# TopLevel.net
KiCad netlist of a schematic drawn in Altium Designer
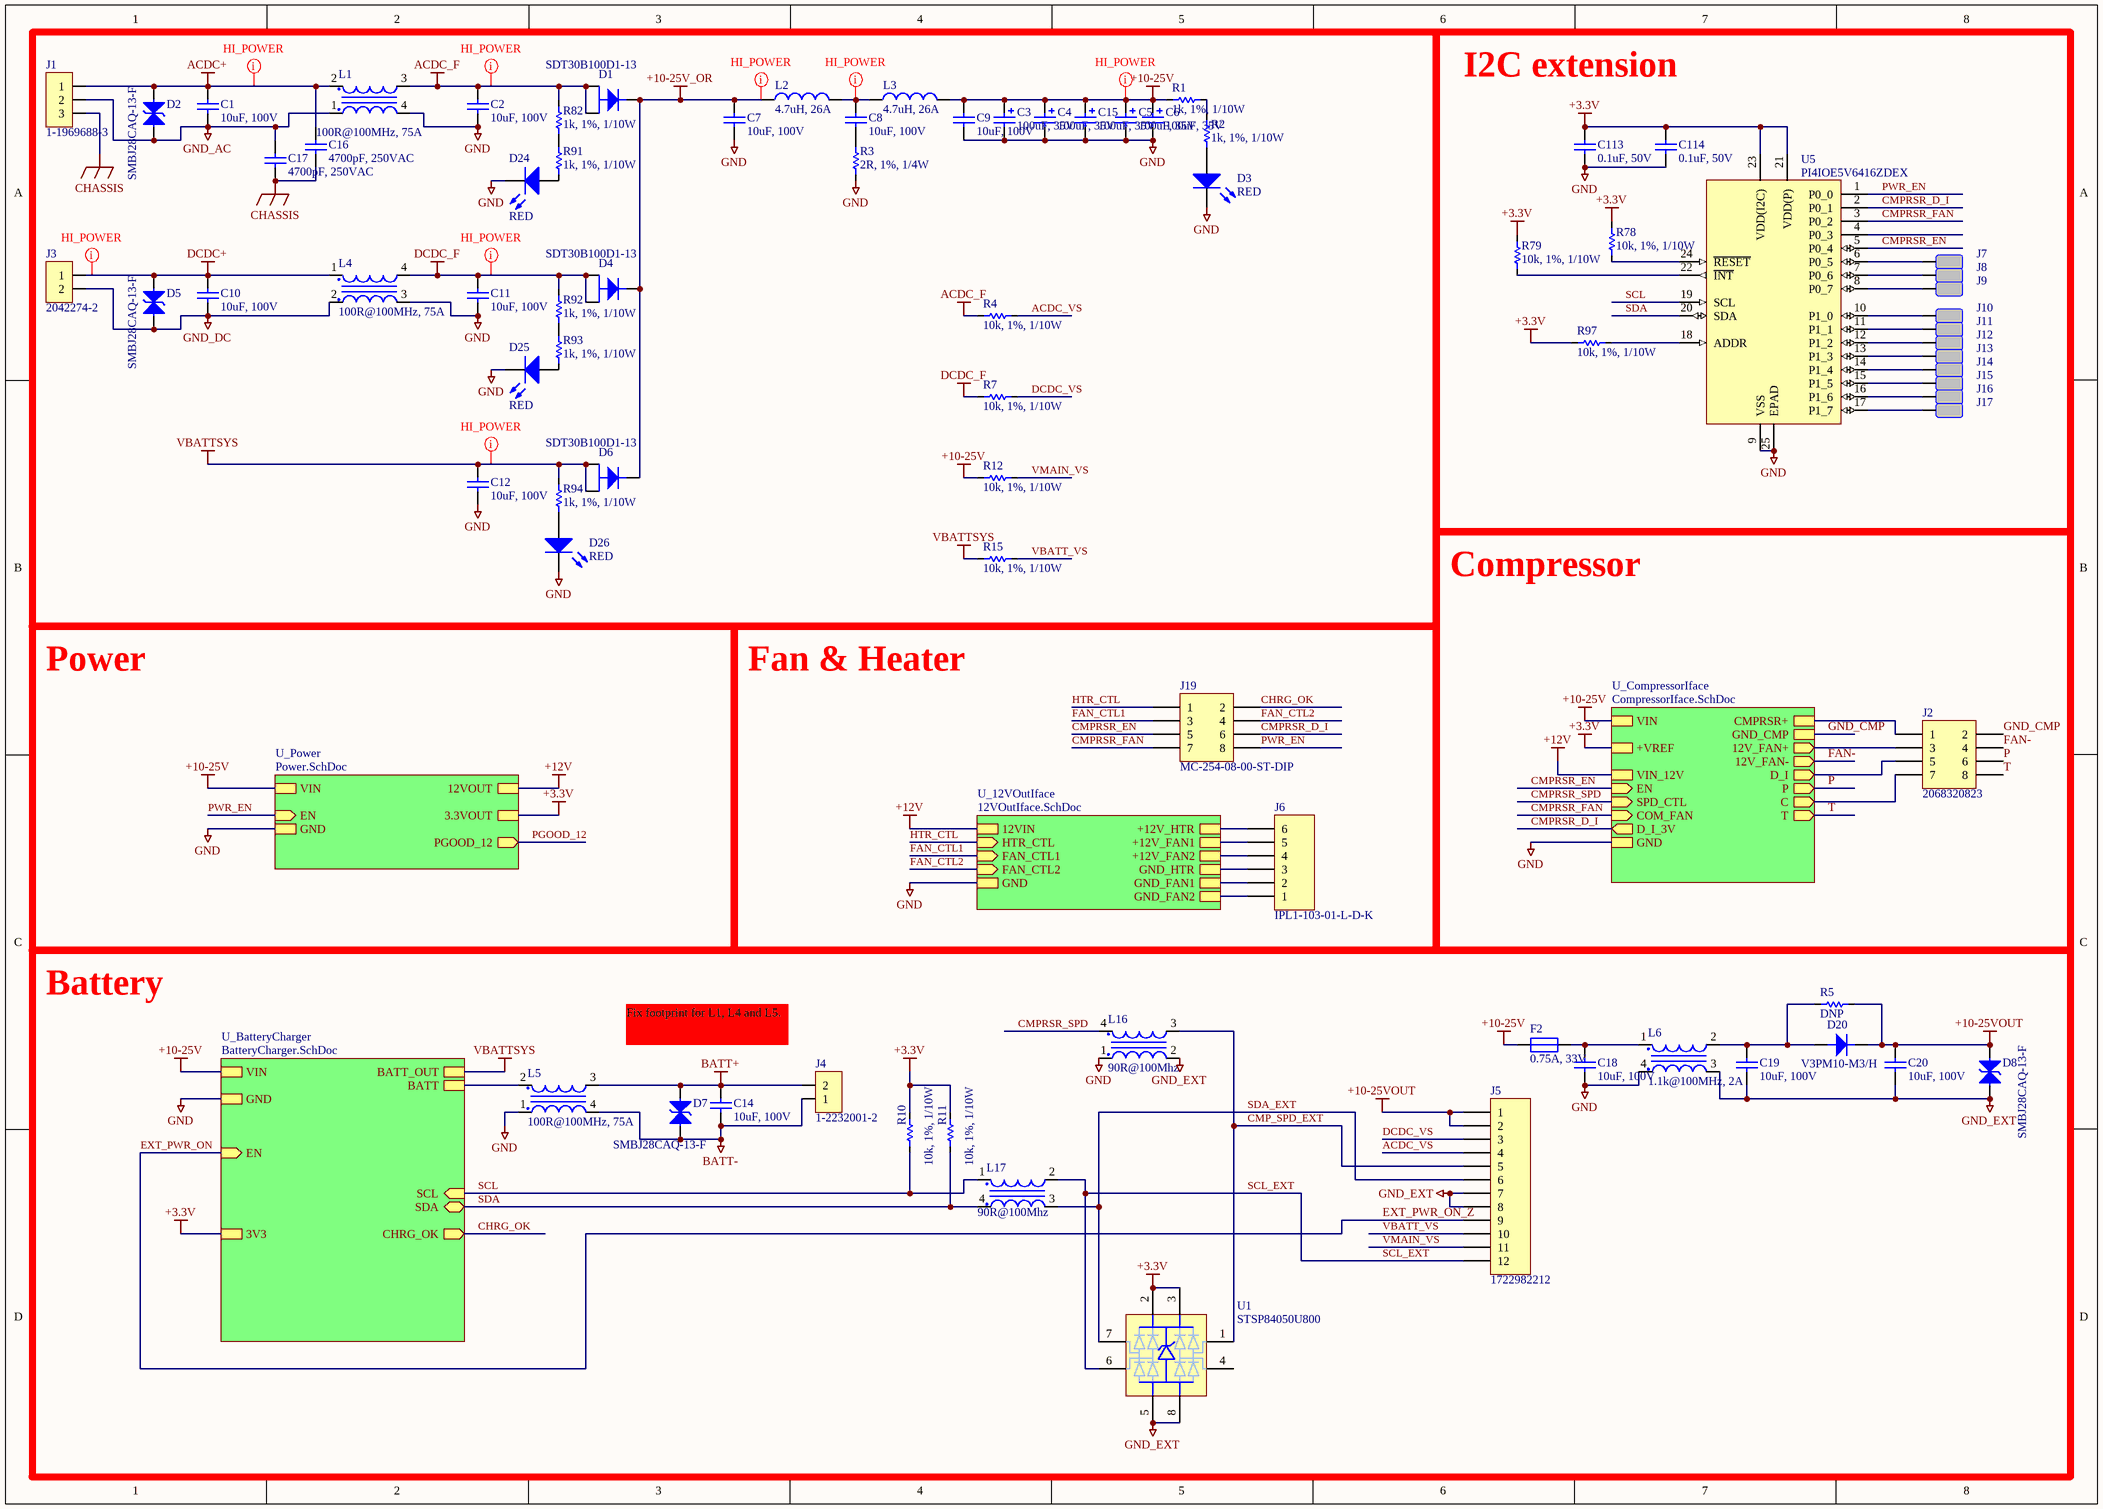
[diagram p0: TopLevel.SchDoc]

(export (version "E")
  (design (tool "Eeschema 10.0.6"))
  (components
    (comp (ref "C1")
      (value "10uF, 100V")
      (footprint "1210")
      (description "MLCC 10UF 100V X7S 1210")
      (fields (field (name "PART NUMBER") "NS00779"))
      (libsource (lib "FullPartsDB") (part "Cap"))
    )
    (comp (ref "C2")
      (value "10uF, 100V")
      (footprint "1210")
      (description "MLCC 10UF 100V X7S 1210")
      (fields (field (name "PART NUMBER") "NS00779"))
      (libsource (lib "FullPartsDB") (part "Cap"))
    )
    (comp (ref "C3")
      (value "100uF, 35V")
      (footprint "CAPAE7866X80L")
      (description "CAP ALUM 100UF 20% 35V SMD")
      (fields (field (name "PART NUMBER") "NS00911"))
      (libsource (lib "FullPartsDB") (part "CAP_POL"))
    )
    (comp (ref "C4")
      (value "100uF, 35V")
      (footprint "CAPAE7866X80L")
      (description "CAP ALUM 100UF 20% 35V SMD")
      (fields (field (name "PART NUMBER") "NS00911"))
      (libsource (lib "FullPartsDB") (part "CAP_POL"))
    )
    (comp (ref "C5")
      (value "100uF, 35V")
      (footprint "CAPAE7866X80L")
      (description "CAP ALUM 100UF 20% 35V SMD")
      (fields (field (name "PART NUMBER") "NS00911"))
      (libsource (lib "FullPartsDB") (part "CAP_POL"))
    )
    (comp (ref "C6")
      (value "100uF, 35V")
      (footprint "CAPAE7866X80L")
      (description "CAP ALUM 100UF 20% 35V SMD")
      (fields (field (name "PART NUMBER") "NS00911"))
      (libsource (lib "FullPartsDB") (part "CAP_POL"))
    )
    (comp (ref "C7")
      (value "10uF, 100V")
      (footprint "1210")
      (description "MLCC 10UF 100V X7S 1210")
      (fields (field (name "PART NUMBER") "NS00779"))
      (libsource (lib "FullPartsDB") (part "Cap"))
    )
    (comp (ref "C8")
      (value "10uF, 100V")
      (footprint "1210")
      (description "MLCC 10UF 100V X7S 1210")
      (fields (field (name "PART NUMBER") "NS00779"))
      (libsource (lib "FullPartsDB") (part "Cap"))
    )
    (comp (ref "C9")
      (value "10uF, 100V")
      (footprint "1210")
      (description "MLCC 10UF 100V X7S 1210")
      (fields (field (name "PART NUMBER") "NS00779"))
      (libsource (lib "FullPartsDB") (part "Cap"))
    )
    (comp (ref "C10")
      (value "10uF, 100V")
      (footprint "1210")
      (description "MLCC 10UF 100V X7S 1210")
      (fields (field (name "PART NUMBER") "NS00779"))
      (libsource (lib "FullPartsDB") (part "Cap"))
    )
    (comp (ref "C11")
      (value "10uF, 100V")
      (footprint "1210")
      (description "MLCC 10UF 100V X7S 1210")
      (fields (field (name "PART NUMBER") "NS00779"))
      (libsource (lib "FullPartsDB") (part "Cap"))
    )
    (comp (ref "C12")
      (value "10uF, 100V")
      (footprint "1210")
      (description "MLCC 10UF 100V X7S 1210")
      (fields (field (name "PART NUMBER") "NS00779"))
      (libsource (lib "FullPartsDB") (part "Cap"))
    )
    (comp (ref "C14")
      (value "10uF, 100V")
      (footprint "1210")
      (description "MLCC 10UF 100V X7S 1210")
      (fields (field (name "PART NUMBER") "NS00779"))
      (libsource (lib "FullPartsDB") (part "Cap"))
    )
    (comp (ref "C15")
      (value "100uF, 35V")
      (footprint "CAPAE7866X80L")
      (description "CAP ALUM 100UF 20% 35V SMD")
      (fields (field (name "PART NUMBER") "NS00911"))
      (libsource (lib "FullPartsDB") (part "CAP_POL"))
    )
    (comp (ref "C16")
      (value "4700pF, 250VAC")
      (footprint "2220-2.5_CAP")
      (description "CAP CER 4700PF 250VAC X7R 2220")
      (fields (field (name "PART NUMBER") "NS00768"))
      (libsource (lib "FullPartsDB") (part "Cap"))
    )
    (comp (ref "C17")
      (value "4700pF, 250VAC")
      (footprint "2220-2.5_CAP")
      (description "CAP CER 4700PF 250VAC X7R 2220")
      (fields (field (name "PART NUMBER") "NS00768"))
      (libsource (lib "FullPartsDB") (part "Cap"))
    )
    (comp (ref "C18")
      (value "10uF, 100V")
      (footprint "1210")
      (description "MLCC 10UF 100V X7S 1210")
      (fields (field (name "PART NUMBER") "NS00779"))
      (libsource (lib "FullPartsDB") (part "Cap"))
    )
    (comp (ref "C19")
      (value "10uF, 100V")
      (footprint "1210")
      (description "MLCC 10UF 100V X7S 1210")
      (fields (field (name "PART NUMBER") "NS00779"))
      (libsource (lib "FullPartsDB") (part "Cap"))
    )
    (comp (ref "C20")
      (value "10uF, 100V")
      (footprint "1210")
      (description "MLCC 10UF 100V X7S 1210")
      (fields (field (name "PART NUMBER") "NS00779"))
      (libsource (lib "FullPartsDB") (part "Cap"))
    )
    (comp (ref "C113")
      (value "0.1uF, 50V")
      (footprint "0603")
      (description "CAP CER 0.1UF 50V X7R 0603")
      (fields (field (name "PART NUMBER") "NS00838"))
      (libsource (lib "FullPartsDB") (part "Cap"))
    )
    (comp (ref "C114")
      (value "0.1uF, 50V")
      (footprint "0603")
      (description "CAP CER 0.1UF 50V X7R 0603")
      (fields (field (name "PART NUMBER") "NS00838"))
      (libsource (lib "FullPartsDB") (part "Cap"))
    )
    (comp (ref "D1")
      (value "SDT30B100D1-13")
      (footprint "DPAK")
      (description "DIODE SCHOTTKY 100V 30A TO252")
      (fields (field (name "PART NUMBER") "NS00785"))
      (libsource (lib "FullPartsDB") (part "Diode_2A"))
    )
    (comp (ref "D2")
      (value "SMBJ28CAQ-13-F")
      (footprint "SMB")
      (description "TVS DIODE 28VWM 45.4VC SMB")
      (fields (field (name "PART NUMBER") "NS00890"))
      (libsource (lib "FullPartsDB") (part "DiodeZenerBiDir"))
    )
    (comp (ref "D3")
      (value "RED")
      (footprint "0603_DIODE_K1A2")
      (description "LED RED CLEAR 1608 SMD")
      (fields (field (name "PART NUMBER") "NS00945"))
      (libsource (lib "FullPartsDB") (part "LED_K1A2"))
    )
    (comp (ref "D4")
      (value "SDT30B100D1-13")
      (footprint "DPAK")
      (description "DIODE SCHOTTKY 100V 30A TO252")
      (fields (field (name "PART NUMBER") "NS00785"))
      (libsource (lib "FullPartsDB") (part "Diode_2A"))
    )
    (comp (ref "D5")
      (value "SMBJ28CAQ-13-F")
      (footprint "SMB")
      (description "TVS DIODE 28VWM 45.4VC SMB")
      (fields (field (name "PART NUMBER") "NS00890"))
      (libsource (lib "FullPartsDB") (part "DiodeZenerBiDir"))
    )
    (comp (ref "D6")
      (value "SDT30B100D1-13")
      (footprint "DPAK")
      (description "DIODE SCHOTTKY 100V 30A TO252")
      (fields (field (name "PART NUMBER") "NS00785"))
      (libsource (lib "FullPartsDB") (part "Diode_2A"))
    )
    (comp (ref "D7")
      (value "SMBJ28CAQ-13-F")
      (footprint "SMB")
      (description "TVS DIODE 28VWM 45.4VC SMB")
      (fields (field (name "PART NUMBER") "NS00890"))
      (libsource (lib "FullPartsDB") (part "DiodeZenerBiDir"))
    )
    (comp (ref "D8")
      (value "SMBJ28CAQ-13-F")
      (footprint "SMB")
      (description "TVS DIODE 28VWM 45.4VC SMB")
      (fields (field (name "PART NUMBER") "NS00890"))
      (libsource (lib "FullPartsDB") (part "DiodeZenerBiDir"))
    )
    (comp (ref "D20")
      (value "V3PM10-M3/H")
      (footprint "SMP")
      (description "SCHOTTKY RECTIFIER 3A 100V SMP")
      (fields (field (name "PART NUMBER") "NS00857"))
      (libsource (lib "FullPartsDB") (part "Diode"))
    )
    (comp (ref "D24")
      (value "RED")
      (footprint "0603_DIODE_K1A2")
      (description "LED RED CLEAR 1608 SMD")
      (fields (field (name "PART NUMBER") "NS00945"))
      (libsource (lib "FullPartsDB") (part "LED_K1A2"))
    )
    (comp (ref "D25")
      (value "RED")
      (footprint "0603_DIODE_K1A2")
      (description "LED RED CLEAR 1608 SMD")
      (fields (field (name "PART NUMBER") "NS00945"))
      (libsource (lib "FullPartsDB") (part "LED_K1A2"))
    )
    (comp (ref "D26")
      (value "RED")
      (footprint "0603_DIODE_K1A2")
      (description "LED RED CLEAR 1608 SMD")
      (fields (field (name "PART NUMBER") "NS00945"))
      (libsource (lib "FullPartsDB") (part "LED_K1A2"))
    )
    (comp (ref "F2")
      (value "0.75A, 33V")
      (footprint "1812_CAP")
      (description "PTC RESET FUSE 33V 750MA 1812")
      (fields (field (name "PART NUMBER") "NS00949"))
      (libsource (lib "FullPartsDB") (part "Fuse"))
    )
    (comp (ref "J1")
      (value "1-1969688-3")
      (footprint "CONN_TE_1-1969688-3")
      (description "CONN HEADER VERT 3POS 6MM")
      (fields (field (name "PART NUMBER") "NS00900"))
      (libsource (lib "FullPartsDB") (part "CONN3"))
    )
    (comp (ref "J2")
      (value "2068320823")
      (footprint "CONN_206832-0823")
      (description "Connector Header Through Hole 8 position 0.118\" (3.00mm)")
      (fields (field (name "PUBLISHER") "Altium Limited"))
      (libsource (lib "Miscellaneous Connectors") (part "Header 4X2"))
    )
    (comp (ref "J3")
      (value "2042274-2")
      (footprint "CONN_TE_2042274-2")
      (description "CONN HEADER 2POS PCB")
      (fields (field (name "PART NUMBER") "NS00791"))
      (libsource (lib "") (part "CONN2_1"))
    )
    (comp (ref "J4")
      (value "1-2232001-2")
      (footprint "CONN_TE_1-2232001-2")
      (description "CONN HEADER VERT 2POS 5MM")
      (fields (field (name "PART NUMBER") "NS00788"))
      (libsource (lib "FullPartsDB") (part "CONN2"))
    )
    (comp (ref "J5")
      (value "1722982212")
      (footprint "CONN_MOLEX_1722982212")
      (description "CONN HEADER VERT 12POS 3.5MM")
      (fields (field (name "PART NUMBER") "NS00894"))
      (libsource (lib "FullPartsDB") (part "CONN12"))
    )
    (comp (ref "J6")
      (value "IPL1-103-01-L-D-K")
      (footprint "CONN_SAMTEC_IPL1-103-XX-X-D")
      (description "CONN HEADER VERT 6POS 2.54MM")
      (fields (field (name "PART NUMBER") "NS00897"))
      (libsource (lib "FullPartsDB") (part "CONN6"))
    )
    (comp (ref "J7")
      (value "1.5x3.5")
      (footprint "PAD_15_35")
      (description "PAD SOLDER 1.5x3.5MM")
      (fields (field (name "PART NUMBER") "NS00465"))
      (libsource (lib "FullPartsDB") (part "PAD"))
    )
    (comp (ref "J8")
      (value "1.5x3.5")
      (footprint "PAD_15_35")
      (description "PAD SOLDER 1.5x3.5MM")
      (fields (field (name "PART NUMBER") "NS00465"))
      (libsource (lib "FullPartsDB") (part "PAD"))
    )
    (comp (ref "J9")
      (value "1.5x3.5")
      (footprint "PAD_15_35")
      (description "PAD SOLDER 1.5x3.5MM")
      (fields (field (name "PART NUMBER") "NS00465"))
      (libsource (lib "FullPartsDB") (part "PAD"))
    )
    (comp (ref "J10")
      (value "1.5x3.5")
      (footprint "PAD_15_35")
      (description "PAD SOLDER 1.5x3.5MM")
      (fields (field (name "PART NUMBER") "NS00465"))
      (libsource (lib "FullPartsDB") (part "PAD"))
    )
    (comp (ref "J11")
      (value "1.5x3.5")
      (footprint "PAD_15_35")
      (description "PAD SOLDER 1.5x3.5MM")
      (fields (field (name "PART NUMBER") "NS00465"))
      (libsource (lib "FullPartsDB") (part "PAD"))
    )
    (comp (ref "J12")
      (value "1.5x3.5")
      (footprint "PAD_15_35")
      (description "PAD SOLDER 1.5x3.5MM")
      (fields (field (name "PART NUMBER") "NS00465"))
      (libsource (lib "FullPartsDB") (part "PAD"))
    )
    (comp (ref "J13")
      (value "1.5x3.5")
      (footprint "PAD_15_35")
      (description "PAD SOLDER 1.5x3.5MM")
      (fields (field (name "PART NUMBER") "NS00465"))
      (libsource (lib "FullPartsDB") (part "PAD"))
    )
    (comp (ref "J14")
      (value "1.5x3.5")
      (footprint "PAD_15_35")
      (description "PAD SOLDER 1.5x3.5MM")
      (fields (field (name "PART NUMBER") "NS00465"))
      (libsource (lib "FullPartsDB") (part "PAD"))
    )
    (comp (ref "J15")
      (value "1.5x3.5")
      (footprint "PAD_15_35")
      (description "PAD SOLDER 1.5x3.5MM")
      (fields (field (name "PART NUMBER") "NS00465"))
      (libsource (lib "FullPartsDB") (part "PAD"))
    )
    (comp (ref "J16")
      (value "1.5x3.5")
      (footprint "PAD_15_35")
      (description "PAD SOLDER 1.5x3.5MM")
      (fields (field (name "PART NUMBER") "NS00465"))
      (libsource (lib "FullPartsDB") (part "PAD"))
    )
    (comp (ref "J17")
      (value "1.5x3.5")
      (footprint "PAD_15_35")
      (description "PAD SOLDER 1.5x3.5MM")
      (fields (field (name "PART NUMBER") "NS00465"))
      (libsource (lib "FullPartsDB") (part "PAD"))
    )
    (comp (ref "J19")
      (value "MC-254-08-00-ST-DIP")
      (footprint "CONN_206832")
      (description "Header, 4-Pin, Dual row")
      (fields (field (name "PUBLISHER") "Altium Limited"))
      (libsource (lib "Miscellaneous Connectors") (part "Header 4X2"))
    )
    (comp (ref "L1")
      (value "100R@100MHz, 75A")
      (footprint "FIL_CM5441Z101B-10")
      (description "CMC 75A 2LN 100 OHM TH")
      (fields (field (name "PART NUMBER") "NS00942"))
      (libsource (lib "") (part "CHOKE_COMMON_ALT_1"))
    )
    (comp (ref "L2")
      (value "4.7uH, 26A")
      (footprint "INDM178169X70N")
      (description "FIXED IND 4.7UH 26A 5.5 MOHM SMD")
      (fields (field (name "PART NUMBER") "NS00854"))
      (libsource (lib "FullPartsDB") (part "Inductor"))
    )
    (comp (ref "L3")
      (value "4.7uH, 26A")
      (footprint "INDM178169X70N")
      (description "FIXED IND 4.7UH 26A 5.5 MOHM SMD")
      (fields (field (name "PART NUMBER") "NS00854"))
      (libsource (lib "FullPartsDB") (part "Inductor"))
    )
    (comp (ref "L4")
      (value "100R@100MHz, 75A")
      (footprint "FIL_CM5441Z101B-10")
      (description "CMC 75A 2LN 100 OHM TH")
      (fields (field (name "PART NUMBER") "NS00942"))
      (libsource (lib "FullPartsDB") (part "CHOKE_COMMON_ALT"))
    )
    (comp (ref "L5")
      (value "100R@100MHz, 75A")
      (footprint "FIL_CM5441Z101B-10")
      (description "CMC 75A 2LN 100 OHM TH")
      (fields (field (name "PART NUMBER") "NS00942"))
      (libsource (lib "") (part "CHOKE_COMMON_ALT_1"))
    )
    (comp (ref "L6")
      (value "1.1k@100MHz, 2A")
      (footprint "PLCC440P435X370X235-4L")
      (description "CMC 2A 2LN 1.1K OHM SMD")
      (fields (field (name "PART NUMBER") "NS00952"))
      (libsource (lib "Schlib1") (part "CHOKE_COMMON_ALT"))
    )
    (comp (ref "L16")
      (value "90R@100Mhz")
      (footprint "BOURNS_SRF2012")
      (description "INDUCTOR COMMON MODE 90 OHM 25%")
      (fields (field (name "PART NUMBER") "NS00042"))
      (libsource (lib "") (part "CHOKE_COMMON_1"))
    )
    (comp (ref "L17")
      (value "90R@100Mhz")
      (footprint "BOURNS_SRF2012")
      (description "INDUCTOR COMMON MODE 90 OHM 25%")
      (fields (field (name "PART NUMBER") "NS00042"))
      (libsource (lib "FullPartsDB") (part "CHOKE_COMMON"))
    )
    (comp (ref "R1")
      (value "1k, 1%, 1/10W")
      (footprint "0603")
      (description "RES 1K OHM 1% 1/10W 0603")
      (fields (field (name "PART NUMBER") "NS00882"))
      (libsource (lib "FullPartsDB") (part "RESISTOR"))
    )
    (comp (ref "R2")
      (value "1k, 1%, 1/10W")
      (footprint "0603")
      (description "RES 1K OHM 1% 1/10W 0603")
      (fields (field (name "PART NUMBER") "NS00882"))
      (libsource (lib "FullPartsDB") (part "RESISTOR"))
    )
    (comp (ref "R3")
      (value "2R, 1%, 1/4W")
      (footprint "1206")
      (description "RES 2 OHM 1% 1/4W 1206")
      (fields (field (name "PART NUMBER") "NS00946"))
      (libsource (lib "FullPartsDB") (part "RESISTOR"))
    )
    (comp (ref "R4")
      (value "10k, 1%, 1/10W")
      (footprint "0603")
      (description "RES 10K OHM 1% 1/10W 0603")
      (fields (field (name "PART NUMBER") "NS00820"))
      (libsource (lib "FullPartsDB") (part "RESISTOR"))
    )
    (comp (ref "R5")
      (value "DNP")
      (footprint "0805")
      (description "RES SMD 0.0 OHM JUMPER 1/2W 0805")
      (fields (field (name "PART NUMBER") "NS00258"))
      (libsource (lib "FullPartsDB") (part "RESISTOR"))
    )
    (comp (ref "R7")
      (value "10k, 1%, 1/10W")
      (footprint "0603")
      (description "RES 10K OHM 1% 1/10W 0603")
      (fields (field (name "PART NUMBER") "NS00820"))
      (libsource (lib "FullPartsDB") (part "RESISTOR"))
    )
    (comp (ref "R10")
      (value "10k, 1%, 1/10W")
      (footprint "0603")
      (description "RES 10K OHM 1% 1/10W 0603")
      (fields (field (name "PART NUMBER") "NS00820"))
      (libsource (lib "FullPartsDB") (part "RESISTOR"))
    )
    (comp (ref "R11")
      (value "10k, 1%, 1/10W")
      (footprint "0603")
      (description "RES 10K OHM 1% 1/10W 0603")
      (fields (field (name "PART NUMBER") "NS00820"))
      (libsource (lib "FullPartsDB") (part "RESISTOR"))
    )
    (comp (ref "R12")
      (value "10k, 1%, 1/10W")
      (footprint "0603")
      (description "RES 10K OHM 1% 1/10W 0603")
      (fields (field (name "PART NUMBER") "NS00820"))
      (libsource (lib "FullPartsDB") (part "RESISTOR"))
    )
    (comp (ref "R15")
      (value "10k, 1%, 1/10W")
      (footprint "0603")
      (description "RES 10K OHM 1% 1/10W 0603")
      (fields (field (name "PART NUMBER") "NS00820"))
      (libsource (lib "FullPartsDB") (part "RESISTOR"))
    )
    (comp (ref "R78")
      (value "10k, 1%, 1/10W")
      (footprint "0603")
      (description "RES 10K OHM 1% 1/10W 0603")
      (fields (field (name "PART NUMBER") "NS00820"))
      (libsource (lib "FullPartsDB") (part "RESISTOR"))
    )
    (comp (ref "R79")
      (value "10k, 1%, 1/10W")
      (footprint "0603")
      (description "RES 10K OHM 1% 1/10W 0603")
      (fields (field (name "PART NUMBER") "NS00820"))
      (libsource (lib "FullPartsDB") (part "RESISTOR"))
    )
    (comp (ref "R82")
      (value "1k, 1%, 1/10W")
      (footprint "0603")
      (description "RES 1K OHM 1% 1/10W 0603")
      (fields (field (name "PART NUMBER") "NS00882"))
      (libsource (lib "FullPartsDB") (part "RESISTOR"))
    )
    (comp (ref "R91")
      (value "1k, 1%, 1/10W")
      (footprint "0603")
      (description "RES 1K OHM 1% 1/10W 0603")
      (fields (field (name "PART NUMBER") "NS00882"))
      (libsource (lib "FullPartsDB") (part "RESISTOR"))
    )
    (comp (ref "R92")
      (value "1k, 1%, 1/10W")
      (footprint "0603")
      (description "RES 1K OHM 1% 1/10W 0603")
      (fields (field (name "PART NUMBER") "NS00882"))
      (libsource (lib "FullPartsDB") (part "RESISTOR"))
    )
    (comp (ref "R93")
      (value "1k, 1%, 1/10W")
      (footprint "0603")
      (description "RES 1K OHM 1% 1/10W 0603")
      (fields (field (name "PART NUMBER") "NS00882"))
      (libsource (lib "FullPartsDB") (part "RESISTOR"))
    )
    (comp (ref "R94")
      (value "1k, 1%, 1/10W")
      (footprint "0603")
      (description "RES 1K OHM 1% 1/10W 0603")
      (fields (field (name "PART NUMBER") "NS00882"))
      (libsource (lib "FullPartsDB") (part "RESISTOR"))
    )
    (comp (ref "R97")
      (value "10k, 1%, 1/10W")
      (footprint "0603")
      (description "RES 10K OHM 1% 1/10W 0603")
      (fields (field (name "PART NUMBER") "NS00820"))
      (libsource (lib "FullPartsDB") (part "RESISTOR"))
    )
    (comp (ref "U1")
      (value "STSP84050U800")
      (footprint "SOIC127P600X163-8N")
      (description "TVS DIODE 5VWM 20VC 8-SOP")
      (fields (field (name "PART NUMBER") "NS00913"))
      (libsource (lib "FullPartsDB") (part "DIODE_STEERING_1++2-34-"))
    )
    (comp (ref "U5")
      (value "PI4IOE5V6416ZDEX")
      (footprint "QFN50P400X400X90_HS-25L")
      (description "IC XPNDR 400KHZ I2C 24TQFN")
      (fields (field (name "PART NUMBER") "NS00947"))
      (libsource (lib "FullPartsDB") (part "DIODES_PI4IOE5V6416"))
    )
  )
  (nets
    (net (code "1") (name "+3.3V") (class "Default")
      (node (ref "C113") (pin "1") (pinfunction "1_1") (pintype "passive"))
      (node (ref "C114") (pin "1") (pinfunction "1_1") (pintype "passive"))
      (node (ref "R10") (pin "1") (pinfunction "1_1") (pintype "passive"))
      (node (ref "R11") (pin "1") (pinfunction "1_1") (pintype "passive"))
      (node (ref "R78") (pin "1") (pinfunction "1_1") (pintype "passive"))
      (node (ref "R79") (pin "1") (pinfunction "1_1") (pintype "passive"))
      (node (ref "R97") (pin "1") (pinfunction "1_1") (pintype "passive"))
      (node (ref "U1") (pin "2") (pintype "passive"))
      (node (ref "U1") (pin "3") (pintype "passive"))
      (node (ref "U5") (pin "21") (pinfunction "VDD(P)_21") (pintype "power_in"))
      (node (ref "U5") (pin "23") (pinfunction "VDD(I2C)_23") (pintype "power_in"))
    )
    (net (code "2") (name "+10-25V") (class "Default")
      (node (ref "C15") (pin "1") (pinfunction "1_1") (pintype "passive"))
      (node (ref "C3") (pin "1") (pinfunction "1_1") (pintype "passive"))
      (node (ref "C4") (pin "1") (pinfunction "1_1") (pintype "passive"))
      (node (ref "C5") (pin "1") (pinfunction "1_1") (pintype "passive"))
      (node (ref "C6") (pin "1") (pinfunction "1_1") (pintype "passive"))
      (node (ref "C9") (pin "2") (pinfunction "2_2") (pintype "passive"))
      (node (ref "F2") (pin "2") (pinfunction "K_2") (pintype "passive"))
      (node (ref "L3") (pin "2") (pinfunction "2_2") (pintype "passive"))
      (node (ref "R1") (pin "2") (pinfunction "2_2") (pintype "passive"))
      (node (ref "R12") (pin "2") (pinfunction "2_2") (pintype "passive"))
    )
    (net (code "3") (name "+10-25VOUT") (class "Default")
      (node (ref "C20") (pin "2") (pinfunction "2_2") (pintype "passive"))
      (node (ref "D20") (pin "2") (pinfunction "K_2") (pintype "passive"))
      (node (ref "D8") (pin "2") (pinfunction "K_2") (pintype "passive"))
      (node (ref "J5") (pin "1") (pinfunction "1_1") (pintype "passive"))
      (node (ref "J5") (pin "2") (pinfunction "2_2") (pintype "passive"))
      (node (ref "R5") (pin "2") (pinfunction "2_2") (pintype "passive"))
    )
    (net (code "4") (name "+10-25V_OR") (class "Default")
      (node (ref "C7") (pin "2") (pinfunction "2_2") (pintype "passive"))
      (node (ref "D1") (pin "2") (pinfunction "K_2") (pintype "passive"))
      (node (ref "D4") (pin "2") (pinfunction "K_2") (pintype "passive"))
      (node (ref "D6") (pin "2") (pinfunction "K_2") (pintype "passive"))
      (node (ref "L2") (pin "1") (pinfunction "1_1") (pintype "passive"))
    )
    (net (code "6") (name "/+12V_FAN1") (class "Default")
      (node (ref "J6") (pin "5") (pinfunction "5_5") (pintype "passive"))
    )
    (net (code "7") (name "/+12V_FAN2") (class "Default")
      (node (ref "J6") (pin "4") (pinfunction "4_4") (pintype "passive"))
    )
    (net (code "8") (name "/+12V_HTR") (class "Default")
      (node (ref "J6") (pin "6") (pinfunction "6_6") (pintype "passive"))
    )
    (net (code "9") (name "/12V_FAN+") (class "Default")
      (node (ref "J2") (pin "3") (pinfunction "3_3") (pintype "passive"))
    )
    (net (code "10") (name "/ACDC_VS") (class "Default")
      (node (ref "J5") (pin "4") (pinfunction "4_4") (pintype "passive"))
      (node (ref "R4") (pin "1") (pinfunction "1_1") (pintype "passive"))
    )
    (net (code "11") (name "/BATT") (class "Default")
      (node (ref "L5") (pin "2") (pinfunction "2_2") (pintype "passive"))
    )
    (net (code "12") (name "/C") (class "Default")
      (node (ref "J2") (pin "7") (pinfunction "7_7") (pintype "passive"))
    )
    (net (code "13") (name "/CHRG_OK") (class "Default")
      (node (ref "J19") (pin "2") (pinfunction "2_2") (pintype "passive"))
    )
    (net (code "14") (name "/CMPRSR+") (class "Default")
      (node (ref "J2") (pin "1") (pinfunction "1_1") (pintype "passive"))
    )
    (net (code "15") (name "/CMPRSR_D_I") (class "Default")
      (node (ref "J19") (pin "6") (pinfunction "6_6") (pintype "passive"))
      (node (ref "U5") (pin "2") (pinfunction "P0_1_2") (pintype "passive"))
    )
    (net (code "16") (name "/CMPRSR_EN") (class "Default")
      (node (ref "J19") (pin "5") (pinfunction "5_5") (pintype "passive"))
      (node (ref "U5") (pin "5") (pinfunction "P0_4_5") (pintype "bidirectional"))
    )
    (net (code "17") (name "/CMPRSR_FAN") (class "Default")
      (node (ref "J19") (pin "7") (pinfunction "7_7") (pintype "passive"))
      (node (ref "U5") (pin "3") (pinfunction "P0_2_3") (pintype "passive"))
    )
    (net (code "18") (name "/CMPRSR_SPD") (class "Default")
      (node (ref "L16") (pin "4") (pinfunction "4_4") (pintype "passive"))
    )
    (net (code "19") (name "/CMP_SPD_EXT") (class "Default")
      (node (ref "J5") (pin "5") (pinfunction "5_5") (pintype "passive"))
      (node (ref "L16") (pin "3") (pinfunction "3_3") (pintype "passive"))
      (node (ref "U1") (pin "1") (pintype "passive"))
    )
    (net (code "20") (name "/DCDC_VS") (class "Default")
      (node (ref "J5") (pin "3") (pinfunction "3_3") (pintype "passive"))
      (node (ref "R7") (pin "1") (pinfunction "1_1") (pintype "passive"))
    )
    (net (code "21") (name "/D_I") (class "Default")
      (node (ref "J2") (pin "5") (pinfunction "5_5") (pintype "passive"))
    )
    (net (code "22") (name "/EXT_PWR_ON") (class "Default")
      (node (ref "J5") (pin "9") (pinfunction "9_9") (pintype "passive"))
    )
    (net (code "23") (name "/FAN-") (class "Default")
      (node (ref "J2") (pin "4") (pinfunction "4_4") (pintype "passive"))
    )
    (net (code "24") (name "/FAN_CTL1") (class "Default")
      (node (ref "J19") (pin "3") (pinfunction "3_3") (pintype "passive"))
    )
    (net (code "25") (name "/FAN_CTL2") (class "Default")
      (node (ref "J19") (pin "4") (pinfunction "4_4") (pintype "passive"))
    )
    (net (code "26") (name "/GND_CMP") (class "Default")
      (node (ref "J2") (pin "2") (pinfunction "2_2") (pintype "passive"))
    )
    (net (code "27") (name "/GND_FAN1") (class "Default")
      (node (ref "J6") (pin "2") (pinfunction "2_2") (pintype "passive"))
    )
    (net (code "28") (name "/GND_FAN2") (class "Default")
      (node (ref "J6") (pin "1") (pinfunction "1_1") (pintype "passive"))
    )
    (net (code "29") (name "/GND_HTR") (class "Default")
      (node (ref "J6") (pin "3") (pinfunction "3_3") (pintype "passive"))
    )
    (net (code "30") (name "/HTR_CTL") (class "Default")
      (node (ref "J19") (pin "1") (pinfunction "1_1") (pintype "passive"))
    )
    (net (code "31") (name "/P") (class "Default")
      (node (ref "J2") (pin "6") (pinfunction "6_6") (pintype "passive"))
    )
    (net (code "33") (name "/PWR_EN") (class "Default")
      (node (ref "J19") (pin "8") (pinfunction "8_8") (pintype "passive"))
      (node (ref "U5") (pin "1") (pinfunction "P0_0_1") (pintype "passive"))
    )
    (net (code "34") (name "/SCL") (class "Default")
      (node (ref "L17") (pin "1") (pinfunction "1_1") (pintype "passive"))
      (node (ref "R10") (pin "2") (pinfunction "2_2") (pintype "passive"))
      (node (ref "U5") (pin "19") (pinfunction "SCL_19") (pintype "input"))
    )
    (net (code "35") (name "/SCL_EXT") (class "Default")
      (node (ref "J5") (pin "12") (pinfunction "12_12") (pintype "passive"))
      (node (ref "L17") (pin "2") (pinfunction "2_2") (pintype "passive"))
      (node (ref "U1") (pin "6") (pintype "passive"))
    )
    (net (code "36") (name "/SDA") (class "Default")
      (node (ref "L17") (pin "4") (pinfunction "4_4") (pintype "passive"))
      (node (ref "R11") (pin "2") (pinfunction "2_2") (pintype "passive"))
      (node (ref "U5") (pin "20") (pinfunction "SDA_20") (pintype "bidirectional"))
    )
    (net (code "37") (name "/SDA_EXT") (class "Default")
      (node (ref "J5") (pin "6") (pinfunction "6_6") (pintype "passive"))
      (node (ref "L17") (pin "3") (pinfunction "3_3") (pintype "passive"))
      (node (ref "U1") (pin "7") (pintype "passive"))
    )
    (net (code "38") (name "/T") (class "Default")
      (node (ref "J2") (pin "8") (pinfunction "8_8") (pintype "passive"))
    )
    (net (code "39") (name "/VBATT_VS") (class "Default")
      (node (ref "J5") (pin "10") (pinfunction "10_10") (pintype "passive"))
      (node (ref "R15") (pin "1") (pinfunction "1_1") (pintype "passive"))
    )
    (net (code "40") (name "/VMAIN_VS") (class "Default")
      (node (ref "J5") (pin "11") (pinfunction "11_11") (pintype "passive"))
      (node (ref "R12") (pin "1") (pinfunction "1_1") (pintype "passive"))
    )
    (net (code "41") (name "ACDC+") (class "Default")
      (node (ref "C1") (pin "2") (pinfunction "2_2") (pintype "passive"))
      (node (ref "C16") (pin "2") (pinfunction "2_2") (pintype "passive"))
      (node (ref "D2") (pin "2") (pinfunction "K_2") (pintype "passive"))
      (node (ref "J1") (pin "1") (pinfunction "1_1") (pintype "passive"))
      (node (ref "L1") (pin "2") (pinfunction "2_2") (pintype "passive"))
    )
    (net (code "42") (name "ACDC_F") (class "Default")
      (node (ref "C2") (pin "2") (pinfunction "2_2") (pintype "passive"))
      (node (ref "D1") (pin "1") (pinfunction "A_1") (pintype "passive"))
      (node (ref "D1") (pin "3") (pinfunction "A_3") (pintype "passive"))
      (node (ref "L1") (pin "3") (pinfunction "3_3") (pintype "passive"))
      (node (ref "R4") (pin "2") (pinfunction "2_2") (pintype "passive"))
      (node (ref "R82") (pin "1") (pinfunction "1_1") (pintype "passive"))
    )
    (net (code "43") (name "BATT+") (class "Default")
      (node (ref "C14") (pin "2") (pinfunction "2_2") (pintype "passive"))
      (node (ref "D7") (pin "2") (pinfunction "K_2") (pintype "passive"))
      (node (ref "J4") (pin "2") (pinfunction "2_2") (pintype "passive"))
      (node (ref "L5") (pin "3") (pinfunction "3_3") (pintype "passive"))
    )
    (net (code "44") (name "BATT-") (class "Default")
      (node (ref "C14") (pin "1") (pinfunction "1_1") (pintype "passive"))
      (node (ref "D7") (pin "1") (pinfunction "A_1") (pintype "passive"))
      (node (ref "J4") (pin "1") (pinfunction "1_1") (pintype "passive"))
      (node (ref "L5") (pin "4") (pinfunction "4_4") (pintype "passive"))
    )
    (net (code "45") (name "CHASSIS") (class "Default")
      (node (ref "C16") (pin "1") (pinfunction "1_1") (pintype "passive"))
      (node (ref "C17") (pin "1") (pinfunction "1_1") (pintype "passive"))
      (node (ref "J1") (pin "3") (pinfunction "3_3") (pintype "passive"))
    )
    (net (code "46") (name "DCDC+") (class "Default")
      (node (ref "C10") (pin "2") (pinfunction "2_2") (pintype "passive"))
      (node (ref "D5") (pin "2") (pinfunction "K_2") (pintype "passive"))
      (node (ref "J3") (pin "1") (pinfunction "1_1") (pintype "passive"))
      (node (ref "L4") (pin "1") (pinfunction "1_1") (pintype "passive"))
    )
    (net (code "47") (name "DCDC_F") (class "Default")
      (node (ref "C11") (pin "2") (pinfunction "2_2") (pintype "passive"))
      (node (ref "D4") (pin "1") (pinfunction "A_1") (pintype "passive"))
      (node (ref "D4") (pin "3") (pinfunction "A_3") (pintype "passive"))
      (node (ref "L4") (pin "4") (pinfunction "4_4") (pintype "passive"))
      (node (ref "R7") (pin "2") (pinfunction "2_2") (pintype "passive"))
      (node (ref "R92") (pin "1") (pinfunction "1_1") (pintype "passive"))
    )
    (net (code "48") (name "GND") (class "Default")
      (node (ref "C11") (pin "1") (pinfunction "1_1") (pintype "passive"))
      (node (ref "C113") (pin "2") (pinfunction "2_2") (pintype "passive"))
      (node (ref "C114") (pin "2") (pinfunction "2_2") (pintype "passive"))
      (node (ref "C12") (pin "1") (pinfunction "1_1") (pintype "passive"))
      (node (ref "C15") (pin "2") (pinfunction "2_2") (pintype "passive"))
      (node (ref "C18") (pin "1") (pinfunction "1_1") (pintype "passive"))
      (node (ref "C2") (pin "1") (pinfunction "1_1") (pintype "passive"))
      (node (ref "C3") (pin "2") (pinfunction "2_2") (pintype "passive"))
      (node (ref "C4") (pin "2") (pinfunction "2_2") (pintype "passive"))
      (node (ref "C5") (pin "2") (pinfunction "2_2") (pintype "passive"))
      (node (ref "C6") (pin "2") (pinfunction "2_2") (pintype "passive"))
      (node (ref "C7") (pin "1") (pinfunction "1_1") (pintype "passive"))
      (node (ref "C9") (pin "1") (pinfunction "1_1") (pintype "passive"))
      (node (ref "D24") (pin "2") (pinfunction "K_2") (pintype "passive"))
      (node (ref "D25") (pin "2") (pinfunction "K_2") (pintype "passive"))
      (node (ref "D26") (pin "2") (pinfunction "K_2") (pintype "passive"))
      (node (ref "D3") (pin "2") (pinfunction "K_2") (pintype "passive"))
      (node (ref "L1") (pin "4") (pinfunction "4_4") (pintype "passive"))
      (node (ref "L16") (pin "1") (pinfunction "1_1") (pintype "passive"))
      (node (ref "L4") (pin "3") (pinfunction "3_3") (pintype "passive"))
      (node (ref "L5") (pin "1") (pinfunction "1_1") (pintype "passive"))
      (node (ref "L6") (pin "4") (pinfunction "4_4") (pintype "passive"))
      (node (ref "R3") (pin "1") (pinfunction "1_1") (pintype "passive"))
      (node (ref "U5") (pin "25") (pinfunction "EPAD_25") (pintype "power_in"))
      (node (ref "U5") (pin "9") (pinfunction "VSS_9") (pintype "power_in"))
    )
    (net (code "49") (name "GND_AC") (class "Default")
      (node (ref "C1") (pin "1") (pinfunction "1_1") (pintype "passive"))
      (node (ref "C17") (pin "2") (pinfunction "2_2") (pintype "passive"))
      (node (ref "D2") (pin "1") (pinfunction "A_1") (pintype "passive"))
      (node (ref "J1") (pin "2") (pinfunction "2_2") (pintype "passive"))
      (node (ref "L1") (pin "1") (pinfunction "1_1") (pintype "passive"))
    )
    (net (code "50") (name "GND_DC") (class "Default")
      (node (ref "C10") (pin "1") (pinfunction "1_1") (pintype "passive"))
      (node (ref "D5") (pin "1") (pinfunction "A_1") (pintype "passive"))
      (node (ref "J3") (pin "2") (pinfunction "2_2") (pintype "passive"))
      (node (ref "L4") (pin "2") (pinfunction "2_2") (pintype "passive"))
    )
    (net (code "51") (name "GND_EXT") (class "Default")
      (node (ref "C19") (pin "1") (pinfunction "1_1") (pintype "passive"))
      (node (ref "C20") (pin "1") (pinfunction "1_1") (pintype "passive"))
      (node (ref "D8") (pin "1") (pinfunction "A_1") (pintype "passive"))
      (node (ref "J5") (pin "7") (pinfunction "7_7") (pintype "passive"))
      (node (ref "J5") (pin "8") (pinfunction "8_8") (pintype "passive"))
      (node (ref "L16") (pin "2") (pinfunction "2_2") (pintype "passive"))
      (node (ref "L6") (pin "3") (pinfunction "3_3") (pintype "passive"))
      (node (ref "U1") (pin "5") (pintype "passive"))
      (node (ref "U1") (pin "8") (pintype "passive"))
    )
    (net (code "52") (name "Net-(C8-Pad1)") (class "Default")
      (node (ref "C8") (pin "1") (pinfunction "1_1") (pintype "passive"))
      (node (ref "R3") (pin "2") (pinfunction "2_2") (pintype "passive"))
    )
    (net (code "53") (name "Net-(C8-Pad2)") (class "Default")
      (node (ref "C8") (pin "2") (pinfunction "2_2") (pintype "passive"))
      (node (ref "L2") (pin "2") (pinfunction "2_2") (pintype "passive"))
      (node (ref "L3") (pin "1") (pinfunction "1_1") (pintype "passive"))
    )
    (net (code "54") (name "Net-(D3-A)") (class "Default")
      (node (ref "D3") (pin "1") (pinfunction "A_1") (pintype "passive"))
      (node (ref "R2") (pin "2") (pinfunction "2_2") (pintype "passive"))
    )
    (net (code "55") (name "Net-(D20-A)") (class "Default")
      (node (ref "C19") (pin "2") (pinfunction "2_2") (pintype "passive"))
      (node (ref "D20") (pin "1") (pinfunction "A_1") (pintype "passive"))
      (node (ref "L6") (pin "2") (pinfunction "2_2") (pintype "passive"))
      (node (ref "R5") (pin "1") (pinfunction "1_1") (pintype "passive"))
    )
    (net (code "56") (name "Net-(D24-A)") (class "Default")
      (node (ref "D24") (pin "1") (pinfunction "A_1") (pintype "passive"))
      (node (ref "R91") (pin "2") (pinfunction "2_2") (pintype "passive"))
    )
    (net (code "57") (name "Net-(D25-A)") (class "Default")
      (node (ref "D25") (pin "1") (pinfunction "A_1") (pintype "passive"))
      (node (ref "R93") (pin "2") (pinfunction "2_2") (pintype "passive"))
    )
    (net (code "58") (name "Net-(D26-A)") (class "Default")
      (node (ref "D26") (pin "1") (pinfunction "A_1") (pintype "passive"))
      (node (ref "R94") (pin "2") (pinfunction "2_2") (pintype "passive"))
    )
    (net (code "59") (name "Net-(F2-A)") (class "Default")
      (node (ref "C18") (pin "2") (pinfunction "2_2") (pintype "passive"))
      (node (ref "F2") (pin "1") (pinfunction "A_1") (pintype "passive"))
      (node (ref "L6") (pin "1") (pinfunction "1_1") (pintype "passive"))
    )
    (net (code "60") (name "Net-(R1-Pad1)") (class "Default")
      (node (ref "R1") (pin "1") (pinfunction "1_1") (pintype "passive"))
      (node (ref "R2") (pin "1") (pinfunction "1_1") (pintype "passive"))
    )
    (net (code "61") (name "Net-(R82-Pad2)") (class "Default")
      (node (ref "R82") (pin "2") (pinfunction "2_2") (pintype "passive"))
      (node (ref "R91") (pin "1") (pinfunction "1_1") (pintype "passive"))
    )
    (net (code "62") (name "Net-(R92-Pad2)") (class "Default")
      (node (ref "R92") (pin "2") (pinfunction "2_2") (pintype "passive"))
      (node (ref "R93") (pin "1") (pinfunction "1_1") (pintype "passive"))
    )
    (net (code "63") (name "Net-(U5-ADDR)") (class "Default")
      (node (ref "R97") (pin "2") (pinfunction "2_2") (pintype "passive"))
      (node (ref "U5") (pin "18") (pinfunction "ADDR_18") (pintype "input"))
    )
    (net (code "64") (name "Net-(U5-INT)") (class "Default")
      (node (ref "R79") (pin "2") (pinfunction "2_2") (pintype "passive"))
      (node (ref "U5") (pin "22") (pinfunction "INT_22") (pintype "output"))
    )
    (net (code "65") (name "Net-(U5-P0_5)") (class "Default")
      (node (ref "J7") (pin "1") (pinfunction "1_1") (pintype "passive"))
      (node (ref "U5") (pin "6") (pinfunction "P0_5_6") (pintype "bidirectional"))
    )
    (net (code "66") (name "Net-(U5-P0_6)") (class "Default")
      (node (ref "J8") (pin "1") (pinfunction "1_1") (pintype "passive"))
      (node (ref "U5") (pin "7") (pinfunction "P0_6_7") (pintype "bidirectional"))
    )
    (net (code "67") (name "Net-(U5-P0_7)") (class "Default")
      (node (ref "J9") (pin "1") (pinfunction "1_1") (pintype "passive"))
      (node (ref "U5") (pin "8") (pinfunction "P0_7_8") (pintype "bidirectional"))
    )
    (net (code "68") (name "Net-(U5-P1_0)") (class "Default")
      (node (ref "J10") (pin "1") (pinfunction "1_1") (pintype "passive"))
      (node (ref "U5") (pin "10") (pinfunction "P1_0_10") (pintype "bidirectional"))
    )
    (net (code "69") (name "Net-(U5-P1_1)") (class "Default")
      (node (ref "J11") (pin "1") (pinfunction "1_1") (pintype "passive"))
      (node (ref "U5") (pin "11") (pinfunction "P1_1_11") (pintype "bidirectional"))
    )
    (net (code "70") (name "Net-(U5-P1_2)") (class "Default")
      (node (ref "J12") (pin "1") (pinfunction "1_1") (pintype "passive"))
      (node (ref "U5") (pin "12") (pinfunction "P1_2_12") (pintype "bidirectional"))
    )
    (net (code "71") (name "Net-(U5-P1_3)") (class "Default")
      (node (ref "J13") (pin "1") (pinfunction "1_1") (pintype "passive"))
      (node (ref "U5") (pin "13") (pinfunction "P1_3_13") (pintype "bidirectional"))
    )
    (net (code "72") (name "Net-(U5-P1_4)") (class "Default")
      (node (ref "J14") (pin "1") (pinfunction "1_1") (pintype "passive"))
      (node (ref "U5") (pin "14") (pinfunction "P1_4_14") (pintype "bidirectional"))
    )
    (net (code "73") (name "Net-(U5-P1_5)") (class "Default")
      (node (ref "J15") (pin "1") (pinfunction "1_1") (pintype "passive"))
      (node (ref "U5") (pin "15") (pinfunction "P1_5_15") (pintype "bidirectional"))
    )
    (net (code "74") (name "Net-(U5-P1_6)") (class "Default")
      (node (ref "J16") (pin "1") (pinfunction "1_1") (pintype "passive"))
      (node (ref "U5") (pin "16") (pinfunction "P1_6_16") (pintype "bidirectional"))
    )
    (net (code "75") (name "Net-(U5-P1_7)") (class "Default")
      (node (ref "J17") (pin "1") (pinfunction "1_1") (pintype "passive"))
      (node (ref "U5") (pin "17") (pinfunction "P1_7_17") (pintype "bidirectional"))
    )
    (net (code "76") (name "Net-(U5-RESET)") (class "Default")
      (node (ref "R78") (pin "2") (pinfunction "2_2") (pintype "passive"))
      (node (ref "U5") (pin "24") (pinfunction "RESET_24") (pintype "input"))
    )
    (net (code "77") (name "VBATTSYS") (class "Default")
      (node (ref "C12") (pin "2") (pinfunction "2_2") (pintype "passive"))
      (node (ref "D6") (pin "1") (pinfunction "A_1") (pintype "passive"))
      (node (ref "D6") (pin "3") (pinfunction "A_3") (pintype "passive"))
      (node (ref "R15") (pin "2") (pinfunction "2_2") (pintype "passive"))
      (node (ref "R94") (pin "1") (pinfunction "1_1") (pintype "passive"))
    )
    (net (code "78") (name "unconnected-(U1-Pad4)") (class "Default")
      (node (ref "U1") (pin "4") (pintype "passive"))
    )
    (net (code "79") (name "unconnected-(U5-P0_3-Pad4)") (class "Default")
      (node (ref "U5") (pin "4") (pinfunction "P0_3_4") (pintype "passive"))
    )
  )
)
